# Segger_JTAG_OptoIso_v1p4.net
KiCad netlist of a schematic drawn in EAGLE
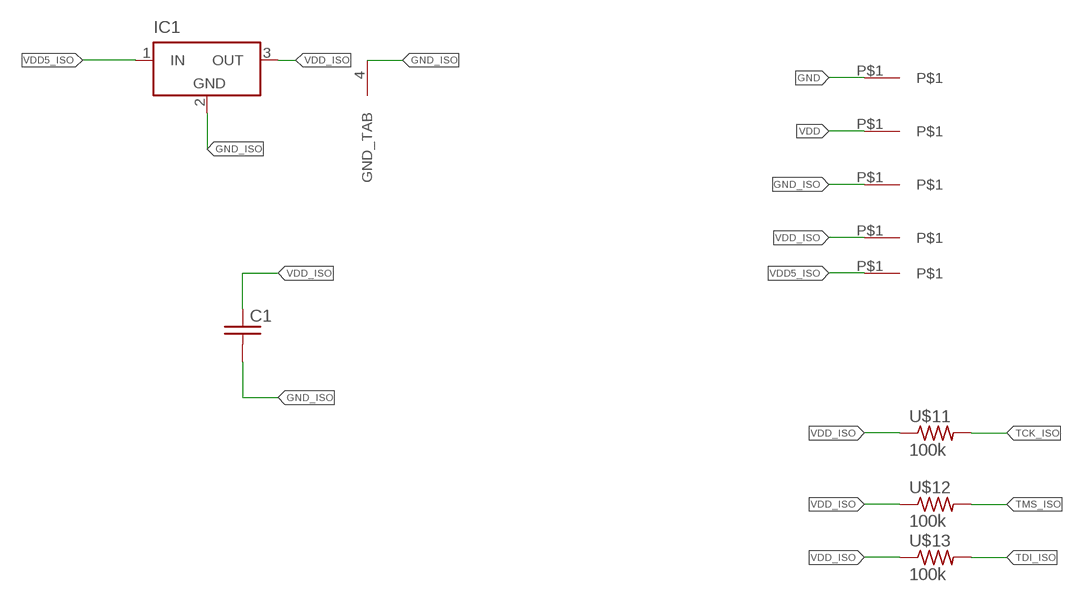
[diagram p0: schematic, sheet 1, part 1 of 2]
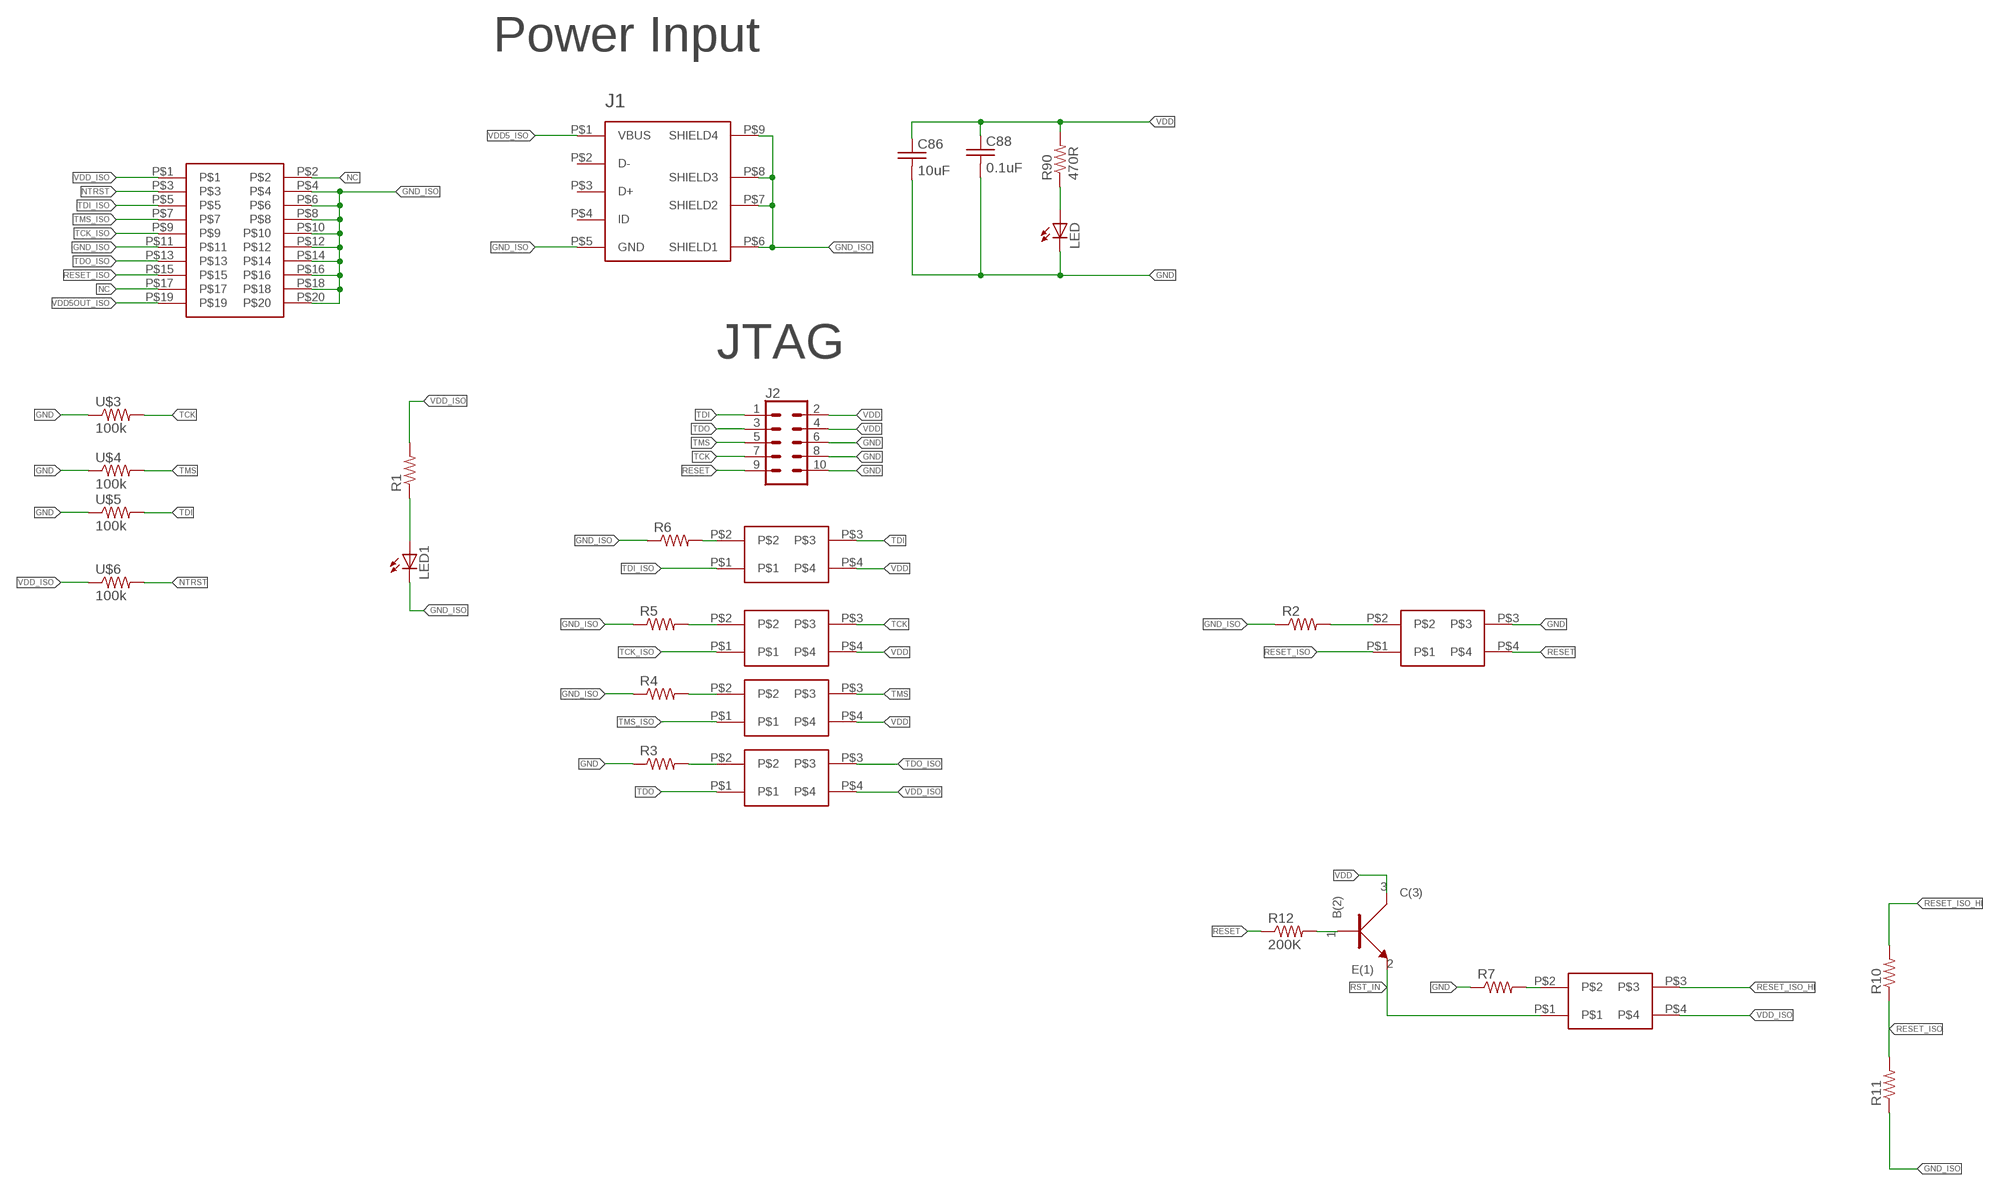
[diagram p1: schematic, sheet 1, part 2 of 2]

(export (version "E")
  (design (tool "Eeschema 10.0.6"))
  (components
    (comp (ref "C1")
      (value "C_0805")
      (footprint "eagle-import:0805")
      (libsource (lib "eagle-import") (part "C_0805"))
    )
    (comp (ref "C86")
      (value "10uF")
      (footprint "eagle-import:0805")
      (libsource (lib "eagle-import") (part "C_0805"))
    )
    (comp (ref "C88")
      (value "0.1uF")
      (footprint "eagle-import:0805")
      (libsource (lib "eagle-import") (part "C_0805"))
    )
    (comp (ref "IC1")
      (value "LT1129CST3")
      (footprint "eagle-import:SOT223")
      (libsource (lib "eagle-import") (part "LT1129CST3"))
    )
    (comp (ref "J1")
      (value "USB_MICRO-B")
      (footprint "eagle-import:USB_MICRO-B")
      (libsource (lib "eagle-import") (part "USB_MICRO-B"))
    )
    (comp (ref "J2")
      (value "CONN_05X2PTH")
      (footprint "eagle-import:2X5")
      (libsource (lib "eagle-import") (part "CONN_05X2PTH"))
    )
    (comp (ref "LED")
      (value "LED_0805_GREEN")
      (footprint "eagle-import:LED_0805_GREEN")
      (libsource (lib "eagle-import") (part "LED_0805_GREEN"))
    )
    (comp (ref "LED1")
      (value "LED_0805_GREEN")
      (footprint "eagle-import:LED_0805_GREEN")
      (libsource (lib "eagle-import") (part "LED_0805_GREEN"))
    )
    (comp (ref "P1")
      (value "1_X_1_1MM_PIN")
      (footprint "eagle-import:1_X_1_1MM_PIN")
      (libsource (lib "eagle-import") (part "1_X_1_1MM_PIN"))
    )
    (comp (ref "P2")
      (value "1_X_1_1MM_PIN")
      (footprint "eagle-import:1_X_1_1MM_PIN")
      (libsource (lib "eagle-import") (part "1_X_1_1MM_PIN"))
    )
    (comp (ref "P3")
      (value "1_X_1_1MM_PIN")
      (footprint "eagle-import:1_X_1_1MM_PIN")
      (libsource (lib "eagle-import") (part "1_X_1_1MM_PIN"))
    )
    (comp (ref "P4")
      (value "1_X_1_1MM_PIN")
      (footprint "eagle-import:1_X_1_1MM_PIN")
      (libsource (lib "eagle-import") (part "1_X_1_1MM_PIN"))
    )
    (comp (ref "P5")
      (value "1_X_1_1MM_PIN")
      (footprint "eagle-import:1_X_1_1MM_PIN")
      (libsource (lib "eagle-import") (part "1_X_1_1MM_PIN"))
    )
    (comp (ref "R1")
      (value "R_0805")
      (footprint "eagle-import:0805")
      (libsource (lib "eagle-import") (part "R_0805"))
    )
    (comp (ref "R2")
      (value "R_0805")
      (footprint "eagle-import:0805")
      (libsource (lib "eagle-import") (part "R_0805"))
    )
    (comp (ref "R3")
      (value "R_0805")
      (footprint "eagle-import:0805")
      (libsource (lib "eagle-import") (part "R_0805"))
    )
    (comp (ref "R4")
      (value "R_0805")
      (footprint "eagle-import:0805")
      (libsource (lib "eagle-import") (part "R_0805"))
    )
    (comp (ref "R5")
      (value "R_0805")
      (footprint "eagle-import:0805")
      (libsource (lib "eagle-import") (part "R_0805"))
    )
    (comp (ref "R6")
      (value "R_0805")
      (footprint "eagle-import:0805")
      (libsource (lib "eagle-import") (part "R_0805"))
    )
    (comp (ref "R7")
      (value "R_0805")
      (footprint "eagle-import:0805")
      (libsource (lib "eagle-import") (part "R_0805"))
    )
    (comp (ref "R10")
      (value "R_0805")
      (footprint "eagle-import:0805")
      (libsource (lib "eagle-import") (part "R_0805"))
    )
    (comp (ref "R11")
      (value "R_0805")
      (footprint "eagle-import:0805")
      (libsource (lib "eagle-import") (part "R_0805"))
    )
    (comp (ref "R12")
      (value "200K")
      (footprint "eagle-import:0402")
      (libsource (lib "eagle-import") (part "R_0402"))
    )
    (comp (ref "R90")
      (value "470R")
      (footprint "eagle-import:0805")
      (libsource (lib "eagle-import") (part "R_0805"))
    )
    (comp (ref "U$1")
      (value "OPTCOUPLER_PS2501L-1")
      (footprint "eagle-import:OPTOCOUPLER_PS2501L-1")
      (libsource (lib "eagle-import") (part "OPTCOUPLER_PS2501L-1"))
    )
    (comp (ref "U$2")
      (value "2_X_10_HEADER_GENERIC")
      (footprint "eagle-import:2_X_10_.1_INCH")
      (libsource (lib "eagle-import") (part "2_X_10_HEADER_GENERIC"))
    )
    (comp (ref "U$3")
      (value "100k")
      (footprint "eagle-import:0805")
      (libsource (lib "eagle-import") (part "R_0805"))
    )
    (comp (ref "U$4")
      (value "100k")
      (footprint "eagle-import:0805")
      (libsource (lib "eagle-import") (part "R_0805"))
    )
    (comp (ref "U$5")
      (value "100k")
      (footprint "eagle-import:0805")
      (libsource (lib "eagle-import") (part "R_0805"))
    )
    (comp (ref "U$6")
      (value "100k")
      (footprint "eagle-import:0805")
      (libsource (lib "eagle-import") (part "R_0805"))
    )
    (comp (ref "U$7")
      (value "OPTCOUPLER_PS2501L-1")
      (footprint "eagle-import:OPTOCOUPLER_PS2501L-1")
      (libsource (lib "eagle-import") (part "OPTCOUPLER_PS2501L-1"))
    )
    (comp (ref "U$8")
      (value "OPTCOUPLER_PS2501L-1")
      (footprint "eagle-import:OPTOCOUPLER_PS2501L-1")
      (libsource (lib "eagle-import") (part "OPTCOUPLER_PS2501L-1"))
    )
    (comp (ref "U$9")
      (value "OPTCOUPLER_PS2501L-1")
      (footprint "eagle-import:OPTOCOUPLER_PS2501L-1")
      (libsource (lib "eagle-import") (part "OPTCOUPLER_PS2501L-1"))
    )
    (comp (ref "U$10")
      (value "OPTCOUPLER_PS2501L-1")
      (footprint "eagle-import:OPTOCOUPLER_PS2501L-1")
      (libsource (lib "eagle-import") (part "OPTCOUPLER_PS2501L-1"))
    )
    (comp (ref "U$11")
      (value "100k")
      (footprint "eagle-import:0805")
      (libsource (lib "eagle-import") (part "R_0805"))
    )
    (comp (ref "U$12")
      (value "100k")
      (footprint "eagle-import:0805")
      (libsource (lib "eagle-import") (part "R_0805"))
    )
    (comp (ref "U$13")
      (value "100k")
      (footprint "eagle-import:0805")
      (libsource (lib "eagle-import") (part "R_0805"))
    )
    (comp (ref "U$14")
      (value "OPTCOUPLER_PS2501L-1")
      (footprint "eagle-import:OPTOCOUPLER_PS2501L-1")
      (libsource (lib "eagle-import") (part "OPTCOUPLER_PS2501L-1"))
    )
    (comp (ref "U4")
      (value "BC846BW")
      (footprint "eagle-import:SOT323")
      (libsource (lib "eagle-import") (part "BC846BW"))
    )
  )
  (nets
    (net (code "1") (name "GND") (class "Default")
      (node (ref "C86") (pin "2") (pinfunction "2_2") (pintype "passive"))
      (node (ref "C88") (pin "2") (pinfunction "2_2") (pintype "passive"))
      (node (ref "J2") (pin "10") (pinfunction "10_10") (pintype "passive"))
      (node (ref "J2") (pin "6") (pinfunction "6_6") (pintype "passive"))
      (node (ref "J2") (pin "8") (pinfunction "8_8") (pintype "passive"))
      (node (ref "LED") (pin "C") (pinfunction "C_C") (pintype "passive"))
      (node (ref "P1") (pin "P$1") (pinfunction "P$1_P$1") (pintype "bidirectional"))
      (node (ref "R3") (pin "1") (pinfunction "1_1") (pintype "passive"))
      (node (ref "R7") (pin "1") (pinfunction "1_1") (pintype "passive"))
      (node (ref "U$10") (pin "P$3") (pinfunction "P$3_P$3") (pintype "bidirectional"))
      (node (ref "U$3") (pin "1") (pinfunction "1_1") (pintype "passive"))
      (node (ref "U$4") (pin "1") (pinfunction "1_1") (pintype "passive"))
      (node (ref "U$5") (pin "1") (pinfunction "1_1") (pintype "passive"))
    )
    (net (code "2") (name "GND_ISO") (class "Default")
      (node (ref "C1") (pin "2") (pinfunction "2_2") (pintype "passive"))
      (node (ref "IC1") (pin "2") (pinfunction "GND_2") (pintype "power_in"))
      (node (ref "IC1") (pin "4") (pinfunction "GND_TAB_4") (pintype "bidirectional"))
      (node (ref "J1") (pin "P$5") (pinfunction "GND_P$5") (pintype "bidirectional"))
      (node (ref "J1") (pin "P$6") (pinfunction "SHIELD1_P$6") (pintype "bidirectional"))
      (node (ref "J1") (pin "P$7") (pinfunction "SHIELD2_P$7") (pintype "bidirectional"))
      (node (ref "J1") (pin "P$8") (pinfunction "SHIELD3_P$8") (pintype "bidirectional"))
      (node (ref "J1") (pin "P$9") (pinfunction "SHIELD4_P$9") (pintype "bidirectional"))
      (node (ref "LED1") (pin "C") (pinfunction "C_C") (pintype "passive"))
      (node (ref "P3") (pin "P$1") (pinfunction "P$1_P$1") (pintype "bidirectional"))
      (node (ref "R11") (pin "1") (pinfunction "1_1") (pintype "passive"))
      (node (ref "R2") (pin "1") (pinfunction "1_1") (pintype "passive"))
      (node (ref "R4") (pin "1") (pinfunction "1_1") (pintype "passive"))
      (node (ref "R5") (pin "1") (pinfunction "1_1") (pintype "passive"))
      (node (ref "R6") (pin "1") (pinfunction "1_1") (pintype "passive"))
      (node (ref "U$2") (pin "P$10") (pinfunction "P$10_P$10") (pintype "bidirectional"))
      (node (ref "U$2") (pin "P$11") (pinfunction "P$11_P$11") (pintype "bidirectional"))
      (node (ref "U$2") (pin "P$12") (pinfunction "P$12_P$12") (pintype "bidirectional"))
      (node (ref "U$2") (pin "P$14") (pinfunction "P$14_P$14") (pintype "bidirectional"))
      (node (ref "U$2") (pin "P$16") (pinfunction "P$16_P$16") (pintype "bidirectional"))
      (node (ref "U$2") (pin "P$18") (pinfunction "P$18_P$18") (pintype "bidirectional"))
      (node (ref "U$2") (pin "P$20") (pinfunction "P$20_P$20") (pintype "bidirectional"))
      (node (ref "U$2") (pin "P$4") (pinfunction "P$4_P$4") (pintype "bidirectional"))
      (node (ref "U$2") (pin "P$6") (pinfunction "P$6_P$6") (pintype "bidirectional"))
      (node (ref "U$2") (pin "P$8") (pinfunction "P$8_P$8") (pintype "bidirectional"))
    )
    (net (code "3") (name "NC") (class "Default")
      (node (ref "U$2") (pin "P$17") (pinfunction "P$17_P$17") (pintype "bidirectional"))
      (node (ref "U$2") (pin "P$2") (pinfunction "P$2_P$2") (pintype "bidirectional"))
    )
    (net (code "4") (name "NTRST") (class "Default")
      (node (ref "U$2") (pin "P$3") (pinfunction "P$3_P$3") (pintype "bidirectional"))
      (node (ref "U$6") (pin "2") (pinfunction "2_2") (pintype "passive"))
    )
    (net (code "5") (name "Net-(LED-PadA)") (class "Default")
      (node (ref "LED") (pin "A") (pinfunction "A_A") (pintype "passive"))
      (node (ref "R90") (pin "1") (pinfunction "1_1") (pintype "passive"))
    )
    (net (code "6") (name "Net-(LED1-PadA)") (class "Default")
      (node (ref "LED1") (pin "A") (pinfunction "A_A") (pintype "passive"))
      (node (ref "R1") (pin "1") (pinfunction "1_1") (pintype "passive"))
    )
    (net (code "7") (name "Net-(R2-Pad2)") (class "Default")
      (node (ref "R2") (pin "2") (pinfunction "2_2") (pintype "passive"))
      (node (ref "U$10") (pin "P$2") (pinfunction "P$2_P$2") (pintype "bidirectional"))
    )
    (net (code "8") (name "Net-(R3-Pad2)") (class "Default")
      (node (ref "R3") (pin "2") (pinfunction "2_2") (pintype "passive"))
      (node (ref "U$9") (pin "P$2") (pinfunction "P$2_P$2") (pintype "bidirectional"))
    )
    (net (code "9") (name "Net-(R4-Pad2)") (class "Default")
      (node (ref "R4") (pin "2") (pinfunction "2_2") (pintype "passive"))
      (node (ref "U$8") (pin "P$2") (pinfunction "P$2_P$2") (pintype "bidirectional"))
    )
    (net (code "10") (name "Net-(R5-Pad2)") (class "Default")
      (node (ref "R5") (pin "2") (pinfunction "2_2") (pintype "passive"))
      (node (ref "U$7") (pin "P$2") (pinfunction "P$2_P$2") (pintype "bidirectional"))
    )
    (net (code "11") (name "Net-(R6-Pad2)") (class "Default")
      (node (ref "R6") (pin "2") (pinfunction "2_2") (pintype "passive"))
      (node (ref "U$1") (pin "P$2") (pinfunction "P$2_P$2") (pintype "bidirectional"))
    )
    (net (code "12") (name "Net-(R7-Pad2)") (class "Default")
      (node (ref "R7") (pin "2") (pinfunction "2_2") (pintype "passive"))
      (node (ref "U$14") (pin "P$2") (pinfunction "P$2_P$2") (pintype "bidirectional"))
    )
    (net (code "13") (name "Net-(R12-2)") (class "Default")
      (node (ref "R12") (pin "P$2") (pinfunction "2_P$2") (pintype "passive"))
      (node (ref "U4") (pin "1") (pinfunction "B(2)_1") (pintype "input"))
    )
    (net (code "14") (name "RESET") (class "Default")
      (node (ref "J2") (pin "9") (pinfunction "9_9") (pintype "passive"))
      (node (ref "R12") (pin "P$1") (pinfunction "1_P$1") (pintype "passive"))
      (node (ref "U$10") (pin "P$4") (pinfunction "P$4_P$4") (pintype "bidirectional"))
    )
    (net (code "15") (name "RESET_ISO") (class "Default")
      (node (ref "R10") (pin "1") (pinfunction "1_1") (pintype "passive"))
      (node (ref "R11") (pin "2") (pinfunction "2_2") (pintype "passive"))
      (node (ref "U$10") (pin "P$1") (pinfunction "P$1_P$1") (pintype "bidirectional"))
      (node (ref "U$2") (pin "P$15") (pinfunction "P$15_P$15") (pintype "bidirectional"))
    )
    (net (code "16") (name "RESET_ISO_HI") (class "Default")
      (node (ref "R10") (pin "2") (pinfunction "2_2") (pintype "passive"))
      (node (ref "U$14") (pin "P$3") (pinfunction "P$3_P$3") (pintype "bidirectional"))
    )
    (net (code "17") (name "RST_IN") (class "Default")
      (node (ref "U$14") (pin "P$1") (pinfunction "P$1_P$1") (pintype "bidirectional"))
      (node (ref "U4") (pin "2") (pinfunction "E(1)_2") (pintype "output"))
    )
    (net (code "18") (name "TCK") (class "Default")
      (node (ref "J2") (pin "7") (pinfunction "7_7") (pintype "passive"))
      (node (ref "U$3") (pin "2") (pinfunction "2_2") (pintype "passive"))
      (node (ref "U$7") (pin "P$3") (pinfunction "P$3_P$3") (pintype "bidirectional"))
    )
    (net (code "19") (name "TCK_ISO") (class "Default")
      (node (ref "U$11") (pin "2") (pinfunction "2_2") (pintype "passive"))
      (node (ref "U$2") (pin "P$9") (pinfunction "P$9_P$9") (pintype "bidirectional"))
      (node (ref "U$7") (pin "P$1") (pinfunction "P$1_P$1") (pintype "bidirectional"))
    )
    (net (code "20") (name "TDI") (class "Default")
      (node (ref "J2") (pin "1") (pinfunction "1_1") (pintype "passive"))
      (node (ref "U$1") (pin "P$3") (pinfunction "P$3_P$3") (pintype "bidirectional"))
      (node (ref "U$5") (pin "2") (pinfunction "2_2") (pintype "passive"))
    )
    (net (code "21") (name "TDI_ISO") (class "Default")
      (node (ref "U$1") (pin "P$1") (pinfunction "P$1_P$1") (pintype "bidirectional"))
      (node (ref "U$13") (pin "2") (pinfunction "2_2") (pintype "passive"))
      (node (ref "U$2") (pin "P$5") (pinfunction "P$5_P$5") (pintype "bidirectional"))
    )
    (net (code "22") (name "TDO") (class "Default")
      (node (ref "J2") (pin "3") (pinfunction "3_3") (pintype "passive"))
      (node (ref "U$9") (pin "P$1") (pinfunction "P$1_P$1") (pintype "bidirectional"))
    )
    (net (code "23") (name "TDO_ISO") (class "Default")
      (node (ref "U$2") (pin "P$13") (pinfunction "P$13_P$13") (pintype "bidirectional"))
      (node (ref "U$9") (pin "P$3") (pinfunction "P$3_P$3") (pintype "bidirectional"))
    )
    (net (code "24") (name "TMS") (class "Default")
      (node (ref "J2") (pin "5") (pinfunction "5_5") (pintype "passive"))
      (node (ref "U$4") (pin "2") (pinfunction "2_2") (pintype "passive"))
      (node (ref "U$8") (pin "P$3") (pinfunction "P$3_P$3") (pintype "bidirectional"))
    )
    (net (code "25") (name "TMS_ISO") (class "Default")
      (node (ref "U$12") (pin "2") (pinfunction "2_2") (pintype "passive"))
      (node (ref "U$2") (pin "P$7") (pinfunction "P$7_P$7") (pintype "bidirectional"))
      (node (ref "U$8") (pin "P$1") (pinfunction "P$1_P$1") (pintype "bidirectional"))
    )
    (net (code "26") (name "VDD") (class "Default")
      (node (ref "C86") (pin "1") (pinfunction "1_1") (pintype "passive"))
      (node (ref "C88") (pin "1") (pinfunction "1_1") (pintype "passive"))
      (node (ref "J2") (pin "2") (pinfunction "2_2") (pintype "passive"))
      (node (ref "J2") (pin "4") (pinfunction "4_4") (pintype "passive"))
      (node (ref "P2") (pin "P$1") (pinfunction "P$1_P$1") (pintype "bidirectional"))
      (node (ref "R90") (pin "2") (pinfunction "2_2") (pintype "passive"))
      (node (ref "U$1") (pin "P$4") (pinfunction "P$4_P$4") (pintype "bidirectional"))
      (node (ref "U$7") (pin "P$4") (pinfunction "P$4_P$4") (pintype "bidirectional"))
      (node (ref "U$8") (pin "P$4") (pinfunction "P$4_P$4") (pintype "bidirectional"))
      (node (ref "U4") (pin "3") (pinfunction "C(3)_3") (pintype "input"))
    )
    (net (code "27") (name "VDD5OUT_ISO") (class "Default")
      (node (ref "U$2") (pin "P$19") (pinfunction "P$19_P$19") (pintype "bidirectional"))
    )
    (net (code "28") (name "VDD5_ISO") (class "Default")
      (node (ref "IC1") (pin "1") (pinfunction "IN_1") (pintype "input"))
      (node (ref "J1") (pin "P$1") (pinfunction "VBUS_P$1") (pintype "bidirectional"))
      (node (ref "P5") (pin "P$1") (pinfunction "P$1_P$1") (pintype "bidirectional"))
    )
    (net (code "29") (name "VDD_ISO") (class "Default")
      (node (ref "C1") (pin "1") (pinfunction "1_1") (pintype "passive"))
      (node (ref "IC1") (pin "3") (pinfunction "OUT_3") (pintype "output"))
      (node (ref "P4") (pin "P$1") (pinfunction "P$1_P$1") (pintype "bidirectional"))
      (node (ref "R1") (pin "2") (pinfunction "2_2") (pintype "passive"))
      (node (ref "U$11") (pin "1") (pinfunction "1_1") (pintype "passive"))
      (node (ref "U$12") (pin "1") (pinfunction "1_1") (pintype "passive"))
      (node (ref "U$13") (pin "1") (pinfunction "1_1") (pintype "passive"))
      (node (ref "U$14") (pin "P$4") (pinfunction "P$4_P$4") (pintype "bidirectional"))
      (node (ref "U$2") (pin "P$1") (pinfunction "P$1_P$1") (pintype "bidirectional"))
      (node (ref "U$6") (pin "1") (pinfunction "1_1") (pintype "passive"))
      (node (ref "U$9") (pin "P$4") (pinfunction "P$4_P$4") (pintype "bidirectional"))
    )
    (net (code "30") (name "unconnected-(J1-D+-PadP$3)") (class "Default")
      (node (ref "J1") (pin "P$3") (pinfunction "D+_P$3") (pintype "bidirectional"))
    )
    (net (code "31") (name "unconnected-(J1-D--PadP$2)") (class "Default")
      (node (ref "J1") (pin "P$2") (pinfunction "D-_P$2") (pintype "bidirectional"))
    )
    (net (code "32") (name "unconnected-(J1-ID-PadP$4)") (class "Default")
      (node (ref "J1") (pin "P$4") (pinfunction "ID_P$4") (pintype "bidirectional"))
    )
  )
)
